# PCB_eLock_G592_J1_only_actuators.net
KiCad netlist of a schematic drawn in EAGLE
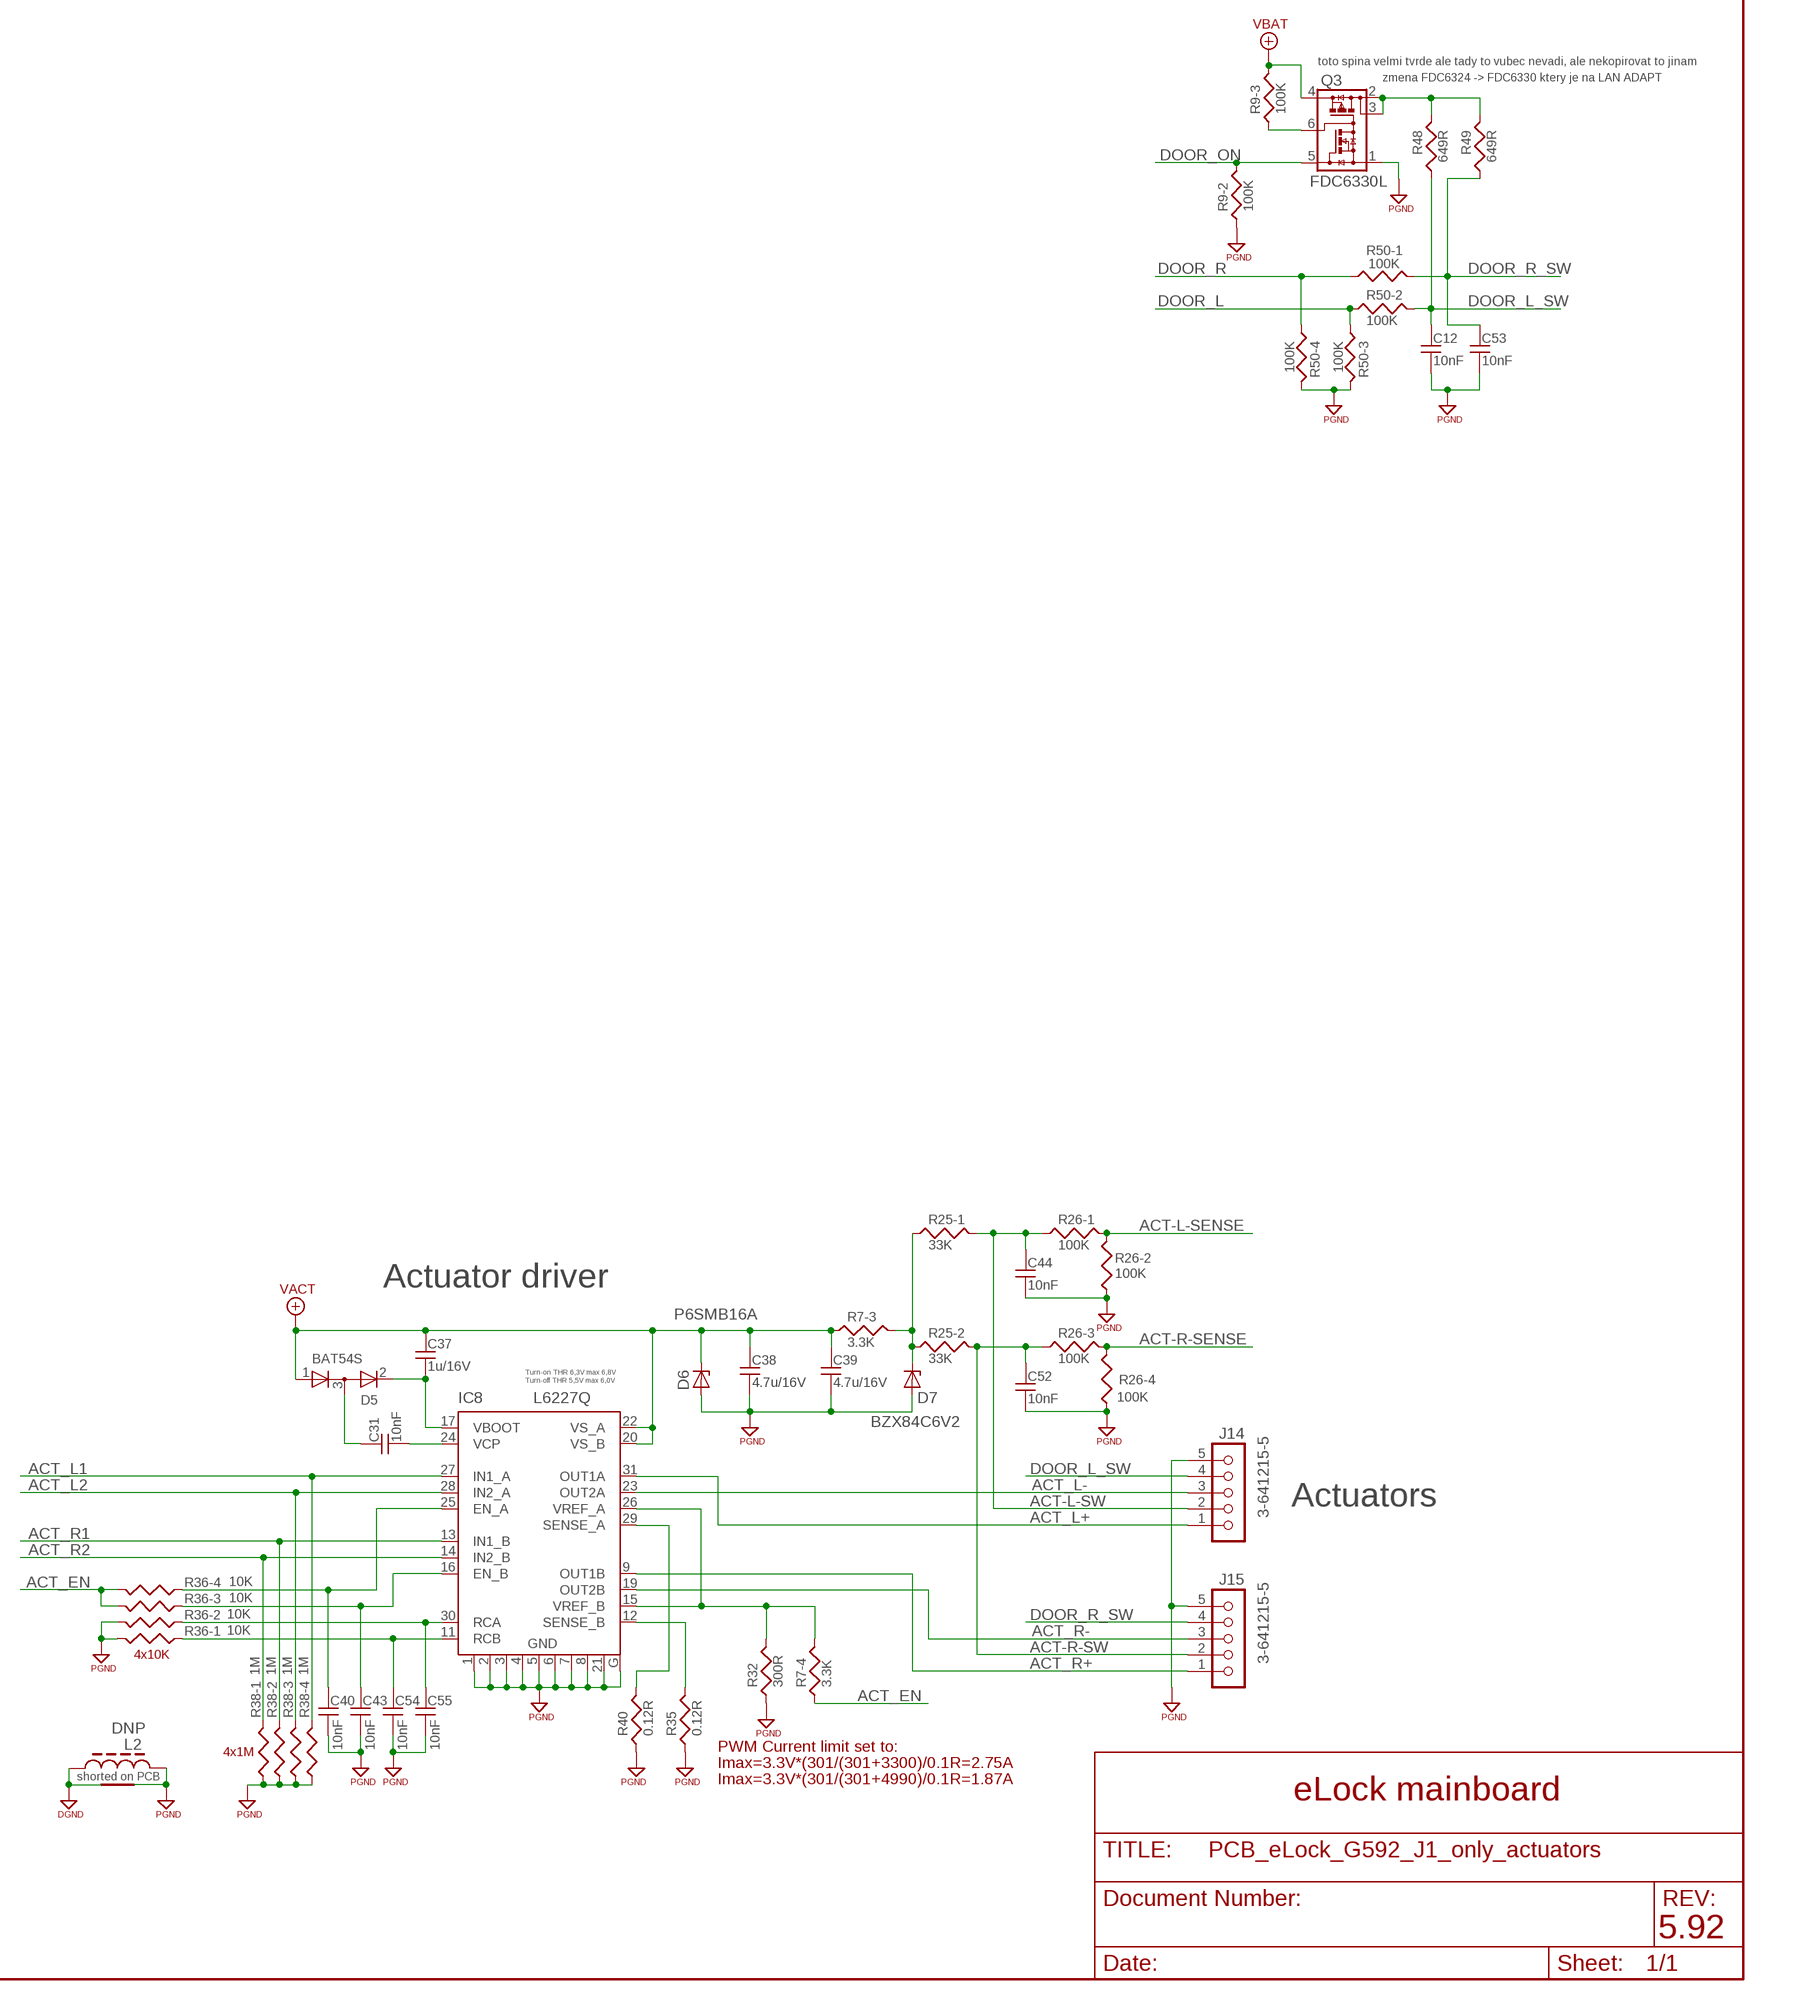
[diagram p0: schematic, sheet 1]

(export (version "E")
  (design (tool "Eeschema 10.0.6"))
  (components
    (comp (ref "C12")
      (value "10nF")
      (footprint "eagle-import:0603")
      (libsource (lib "eagle-import") (part "C-0603"))
    )
    (comp (ref "C31")
      (value "10nF")
      (footprint "eagle-import:0603")
      (libsource (lib "eagle-import") (part "C-0603"))
    )
    (comp (ref "C37")
      (value "1u/16V")
      (footprint "eagle-import:0603")
      (libsource (lib "eagle-import") (part "C-0603"))
    )
    (comp (ref "C38")
      (value "4.7u/16V")
      (footprint "eagle-import:0805")
      (libsource (lib "eagle-import") (part "C-0805"))
    )
    (comp (ref "C39")
      (value "4.7u/16V")
      (footprint "eagle-import:0805")
      (libsource (lib "eagle-import") (part "C-0805"))
    )
    (comp (ref "C40")
      (value "10nF")
      (footprint "eagle-import:0603")
      (libsource (lib "eagle-import") (part "C-0603"))
    )
    (comp (ref "C43")
      (value "10nF")
      (footprint "eagle-import:0603")
      (libsource (lib "eagle-import") (part "C-0603"))
    )
    (comp (ref "C44")
      (value "10nF")
      (footprint "eagle-import:0603")
      (libsource (lib "eagle-import") (part "C-0603"))
    )
    (comp (ref "C52")
      (value "10nF")
      (footprint "eagle-import:0603")
      (libsource (lib "eagle-import") (part "C-0603"))
    )
    (comp (ref "C53")
      (value "10nF")
      (footprint "eagle-import:0603")
      (libsource (lib "eagle-import") (part "C-0603"))
    )
    (comp (ref "C54")
      (value "10nF")
      (footprint "eagle-import:0603")
      (libsource (lib "eagle-import") (part "C-0603"))
    )
    (comp (ref "C55")
      (value "10nF")
      (footprint "eagle-import:0603")
      (libsource (lib "eagle-import") (part "C-0603"))
    )
    (comp (ref "D5")
      (value "BAT54S")
      (footprint "eagle-import:SOT-23")
      (libsource (lib "eagle-import") (part "BAT54S"))
    )
    (comp (ref "D6")
      (value "P6SMB16A")
      (footprint "eagle-import:SMB")
      (libsource (lib "eagle-import") (part "P6SMB16A"))
    )
    (comp (ref "D7")
      (value "BZX84C6V2")
      (footprint "eagle-import:SOT-23")
      (libsource (lib "eagle-import") (part "BZX84C6V2"))
    )
    (comp (ref "IC8")
      (value "L6227Q")
      (footprint "eagle-import:SQFP-S-5X5-32")
      (libsource (lib "eagle-import") (part "L6227Q"))
    )
    (comp (ref "J14")
      (value "3-641215-5")
      (footprint "eagle-import:3-641215-5")
      (libsource (lib "eagle-import") (part "3-641215-5"))
    )
    (comp (ref "J15")
      (value "3-641215-5")
      (footprint "eagle-import:3-641215-5")
      (libsource (lib "eagle-import") (part "3-641215-5"))
    )
    (comp (ref "L2")
      (value "DNP")
      (footprint "eagle-import:0805-0RTOP")
      (libsource (lib "eagle-import") (part "L-0805-0R"))
    )
    (comp (ref "Q3")
      (value "FDC6330L")
      (footprint "eagle-import:SSOT-6")
      (libsource (lib "eagle-import") (part "FDC6324L"))
    )
    (comp (ref "R7")
      (value "3.3K")
      (footprint "eagle-import:0603-ARRAY")
      (libsource (lib "eagle-import") (part "EXB-38"))
    )
    (comp (ref "R9")
      (value "100K")
      (footprint "eagle-import:0603-ARRAY")
      (libsource (lib "eagle-import") (part "EXB-38"))
    )
    (comp (ref "R25")
      (value "33K")
      (footprint "eagle-import:0603-ARRAY")
      (libsource (lib "eagle-import") (part "EXB-38"))
    )
    (comp (ref "R26")
      (value "100K")
      (footprint "eagle-import:0603-ARRAY")
      (libsource (lib "eagle-import") (part "EXB-38"))
    )
    (comp (ref "R32")
      (value "300R")
      (footprint "eagle-import:0603")
      (libsource (lib "eagle-import") (part "R-0603"))
    )
    (comp (ref "R35")
      (value "0.12R")
      (footprint "eagle-import:0805")
      (libsource (lib "eagle-import") (part "R-0805"))
    )
    (comp (ref "R36")
      (value "10K")
      (footprint "eagle-import:0603-ARRAY")
      (libsource (lib "eagle-import") (part "EXB-38"))
    )
    (comp (ref "R38")
      (value "1M")
      (footprint "eagle-import:0603-ARRAY")
      (libsource (lib "eagle-import") (part "EXB-38"))
    )
    (comp (ref "R40")
      (value "0.12R")
      (footprint "eagle-import:0805")
      (libsource (lib "eagle-import") (part "R-0805"))
    )
    (comp (ref "R48")
      (value "649R")
      (footprint "eagle-import:0603")
      (libsource (lib "eagle-import") (part "R-0603"))
    )
    (comp (ref "R49")
      (value "649R")
      (footprint "eagle-import:0603")
      (libsource (lib "eagle-import") (part "R-0603"))
    )
    (comp (ref "R50")
      (value "100K")
      (footprint "eagle-import:0603-ARRAY")
      (libsource (lib "eagle-import") (part "EXB-38"))
    )
  )
  (nets
    (net (code "1") (name "/ACT-L-SENSE") (class "Default")
      (node (ref "R26") (pin "7") (pinfunction "2_7") (pintype "passive"))
      (node (ref "R26") (pin "8") (pinfunction "2_8") (pintype "passive"))
    )
    (net (code "2") (name "/ACT-L-SW") (class "Default")
      (node (ref "C44") (pin "1") (pinfunction "1_1") (pintype "passive"))
      (node (ref "J14") (pin "2") (pinfunction "2_2") (pintype "passive"))
      (node (ref "R25") (pin "8") (pinfunction "2_8") (pintype "passive"))
      (node (ref "R26") (pin "1") (pinfunction "1_1") (pintype "passive"))
    )
    (net (code "3") (name "/ACT-R-SENSE") (class "Default")
      (node (ref "R26") (pin "5") (pinfunction "2_5") (pintype "passive"))
      (node (ref "R26") (pin "6") (pinfunction "2_6") (pintype "passive"))
    )
    (net (code "4") (name "/ACT-R-SW") (class "Default")
      (node (ref "C52") (pin "1") (pinfunction "1_1") (pintype "passive"))
      (node (ref "J15") (pin "2") (pinfunction "2_2") (pintype "passive"))
      (node (ref "R25") (pin "7") (pinfunction "2_7") (pintype "passive"))
      (node (ref "R26") (pin "3") (pinfunction "1_3") (pintype "passive"))
    )
    (net (code "5") (name "/ACT_EN") (class "Default")
      (node (ref "R36") (pin "5") (pinfunction "2_5") (pintype "passive"))
      (node (ref "R36") (pin "6") (pinfunction "2_6") (pintype "passive"))
      (node (ref "R7") (pin "4") (pinfunction "1_4") (pintype "passive"))
    )
    (net (code "6") (name "/ACT_L+") (class "Default")
      (node (ref "IC8") (pin "31") (pinfunction "OUT1A_31") (pintype "output"))
      (node (ref "J14") (pin "1") (pinfunction "1_1") (pintype "passive"))
    )
    (net (code "7") (name "/ACT_L-") (class "Default")
      (node (ref "IC8") (pin "23") (pinfunction "OUT2A_23") (pintype "output"))
      (node (ref "J14") (pin "3") (pinfunction "3_3") (pintype "passive"))
    )
    (net (code "8") (name "/ACT_L1") (class "Default")
      (node (ref "IC8") (pin "27") (pinfunction "IN1_A_27") (pintype "input"))
      (node (ref "R38") (pin "5") (pinfunction "2_5") (pintype "passive"))
    )
    (net (code "9") (name "/ACT_L2") (class "Default")
      (node (ref "IC8") (pin "28") (pinfunction "IN2_A_28") (pintype "input"))
      (node (ref "R38") (pin "6") (pinfunction "2_6") (pintype "passive"))
    )
    (net (code "10") (name "/ACT_R+") (class "Default")
      (node (ref "IC8") (pin "9") (pinfunction "OUT1B_9") (pintype "output"))
      (node (ref "J15") (pin "1") (pinfunction "1_1") (pintype "passive"))
    )
    (net (code "11") (name "/ACT_R-") (class "Default")
      (node (ref "IC8") (pin "19") (pinfunction "OUT2B_19") (pintype "output"))
      (node (ref "J15") (pin "3") (pinfunction "3_3") (pintype "passive"))
    )
    (net (code "12") (name "/ACT_R1") (class "Default")
      (node (ref "IC8") (pin "13") (pinfunction "IN1_B_13") (pintype "input"))
      (node (ref "R38") (pin "7") (pinfunction "2_7") (pintype "passive"))
    )
    (net (code "13") (name "/ACT_R2") (class "Default")
      (node (ref "IC8") (pin "14") (pinfunction "IN2_B_14") (pintype "input"))
      (node (ref "R38") (pin "8") (pinfunction "2_8") (pintype "passive"))
    )
    (net (code "14") (name "/DOOR_L") (class "Default")
      (node (ref "R50") (pin "2") (pinfunction "1_2") (pintype "passive"))
      (node (ref "R50") (pin "3") (pinfunction "1_3") (pintype "passive"))
    )
    (net (code "15") (name "/DOOR_L_SW") (class "Default")
      (node (ref "C12") (pin "1") (pinfunction "1_1") (pintype "passive"))
      (node (ref "J14") (pin "4") (pinfunction "4_4") (pintype "passive"))
      (node (ref "R48") (pin "2") (pinfunction "2_2") (pintype "passive"))
      (node (ref "R50") (pin "7") (pinfunction "2_7") (pintype "passive"))
    )
    (net (code "16") (name "/DOOR_ON") (class "Default")
      (node (ref "Q3") (pin "5") (pinfunction "Q1G_5") (pintype "input"))
      (node (ref "R9") (pin "7") (pinfunction "2_7") (pintype "passive"))
    )
    (net (code "17") (name "/DOOR_R") (class "Default")
      (node (ref "R50") (pin "1") (pinfunction "1_1") (pintype "passive"))
      (node (ref "R50") (pin "4") (pinfunction "1_4") (pintype "passive"))
    )
    (net (code "18") (name "/DOOR_R_SW") (class "Default")
      (node (ref "C53") (pin "1") (pinfunction "1_1") (pintype "passive"))
      (node (ref "J15") (pin "4") (pinfunction "4_4") (pintype "passive"))
      (node (ref "R49") (pin "2") (pinfunction "2_2") (pintype "passive"))
      (node (ref "R50") (pin "8") (pinfunction "2_8") (pintype "passive"))
    )
    (net (code "19") (name "DGND") (class "Default")
      (node (ref "L2") (pin "2") (pinfunction "2_2") (pintype "passive"))
    )
    (net (code "20") (name "Net-(D5-K)") (class "Default")
      (node (ref "C37") (pin "2") (pinfunction "2_2") (pintype "passive"))
      (node (ref "D5") (pin "2") (pinfunction "K_2") (pintype "passive"))
      (node (ref "IC8") (pin "17") (pinfunction "VBOOT_17") (pintype "input"))
    )
    (net (code "21") (name "Net-(D5-KA)") (class "Default")
      (node (ref "C31") (pin "1") (pinfunction "1_1") (pintype "passive"))
      (node (ref "D5") (pin "3") (pinfunction "KA_3") (pintype "passive"))
    )
    (net (code "22") (name "Net-(D7-C)") (class "Default")
      (node (ref "D7") (pin "3") (pinfunction "C_3") (pintype "passive"))
      (node (ref "R25") (pin "1") (pinfunction "1_1") (pintype "passive"))
      (node (ref "R25") (pin "2") (pinfunction "1_2") (pintype "passive"))
      (node (ref "R7") (pin "6") (pinfunction "2_6") (pintype "passive"))
    )
    (net (code "23") (name "Net-(IC8-EN_A)") (class "Default")
      (node (ref "C40") (pin "1") (pinfunction "1_1") (pintype "passive"))
      (node (ref "IC8") (pin "25") (pinfunction "EN_A_25") (pintype "input"))
      (node (ref "R36") (pin "4") (pinfunction "1_4") (pintype "passive"))
    )
    (net (code "24") (name "Net-(IC8-EN_B)") (class "Default")
      (node (ref "C43") (pin "1") (pinfunction "1_1") (pintype "passive"))
      (node (ref "IC8") (pin "16") (pinfunction "EN_B_16") (pintype "input"))
      (node (ref "R36") (pin "3") (pinfunction "1_3") (pintype "passive"))
    )
    (net (code "25") (name "Net-(IC8-RCA)") (class "Default")
      (node (ref "C55") (pin "1") (pinfunction "1_1") (pintype "passive"))
      (node (ref "IC8") (pin "30") (pinfunction "RCA_30") (pintype "input"))
      (node (ref "R36") (pin "2") (pinfunction "1_2") (pintype "passive"))
    )
    (net (code "26") (name "Net-(IC8-RCB)") (class "Default")
      (node (ref "C54") (pin "1") (pinfunction "1_1") (pintype "passive"))
      (node (ref "IC8") (pin "11") (pinfunction "RCB_11") (pintype "input"))
      (node (ref "R36") (pin "1") (pinfunction "1_1") (pintype "passive"))
    )
    (net (code "27") (name "Net-(IC8-SENSE_A)") (class "Default")
      (node (ref "IC8") (pin "29") (pinfunction "SENSE_A_29") (pintype "input"))
      (node (ref "R40") (pin "2") (pinfunction "2_2") (pintype "passive"))
    )
    (net (code "28") (name "Net-(IC8-SENSE_B)") (class "Default")
      (node (ref "IC8") (pin "12") (pinfunction "SENSE_B_12") (pintype "input"))
      (node (ref "R35") (pin "2") (pinfunction "2_2") (pintype "passive"))
    )
    (net (code "29") (name "Net-(IC8-VCP)") (class "Default")
      (node (ref "C31") (pin "2") (pinfunction "2_2") (pintype "passive"))
      (node (ref "IC8") (pin "24") (pinfunction "VCP_24") (pintype "input"))
    )
    (net (code "30") (name "Net-(IC8-VREF_A)") (class "Default")
      (node (ref "IC8") (pin "15") (pinfunction "VREF_B_15") (pintype "input"))
      (node (ref "IC8") (pin "26") (pinfunction "VREF_A_26") (pintype "input"))
      (node (ref "R32") (pin "2") (pinfunction "2_2") (pintype "passive"))
      (node (ref "R7") (pin "5") (pinfunction "2_5") (pintype "passive"))
    )
    (net (code "31") (name "Net-(Q3-Q2D1)") (class "Default")
      (node (ref "Q3") (pin "2") (pinfunction "Q2D1_2") (pintype "bidirectional"))
      (node (ref "Q3") (pin "3") (pinfunction "Q2D2_3") (pintype "bidirectional"))
      (node (ref "R48") (pin "1") (pinfunction "1_1") (pintype "passive"))
      (node (ref "R49") (pin "1") (pinfunction "1_1") (pintype "passive"))
    )
    (net (code "32") (name "Net-(Q3-Q2G)") (class "Default")
      (node (ref "Q3") (pin "6") (pinfunction "Q2G_6") (pintype "input"))
      (node (ref "R9") (pin "3") (pinfunction "1_3") (pintype "passive"))
    )
    (net (code "33") (name "PGND") (class "Default")
      (node (ref "C12") (pin "2") (pinfunction "2_2") (pintype "passive"))
      (node (ref "C38") (pin "2") (pinfunction "2_2") (pintype "passive"))
      (node (ref "C39") (pin "2") (pinfunction "2_2") (pintype "passive"))
      (node (ref "C40") (pin "2") (pinfunction "2_2") (pintype "passive"))
      (node (ref "C43") (pin "2") (pinfunction "2_2") (pintype "passive"))
      (node (ref "C44") (pin "2") (pinfunction "2_2") (pintype "passive"))
      (node (ref "C52") (pin "2") (pinfunction "2_2") (pintype "passive"))
      (node (ref "C53") (pin "2") (pinfunction "2_2") (pintype "passive"))
      (node (ref "C54") (pin "2") (pinfunction "2_2") (pintype "passive"))
      (node (ref "C55") (pin "2") (pinfunction "2_2") (pintype "passive"))
      (node (ref "D6") (pin "A") (pinfunction "A_A") (pintype "passive"))
      (node (ref "D7") (pin "1") (pinfunction "A_1") (pintype "passive"))
      (node (ref "IC8") (pin "1") (pinfunction "GND1_1") (pintype "input"))
      (node (ref "IC8") (pin "2") (pinfunction "GND2_2") (pintype "input"))
      (node (ref "IC8") (pin "21") (pinfunction "GND21_21") (pintype "input"))
      (node (ref "IC8") (pin "3") (pinfunction "GND3_3") (pintype "input"))
      (node (ref "IC8") (pin "4") (pinfunction "GND4_4") (pintype "input"))
      (node (ref "IC8") (pin "5") (pinfunction "GND5_5") (pintype "input"))
      (node (ref "IC8") (pin "6") (pinfunction "GND6_6") (pintype "input"))
      (node (ref "IC8") (pin "7") (pinfunction "GND7_7") (pintype "input"))
      (node (ref "IC8") (pin "8") (pinfunction "GND8_8") (pintype "input"))
      (node (ref "IC8") (pin "G") (pinfunction "GNEXP_G") (pintype "input"))
      (node (ref "J14") (pin "5") (pinfunction "5_5") (pintype "passive"))
      (node (ref "J15") (pin "5") (pinfunction "5_5") (pintype "passive"))
      (node (ref "L2") (pin "1") (pinfunction "1_1") (pintype "passive"))
      (node (ref "Q3") (pin "1") (pinfunction "Q1S_1") (pintype "bidirectional"))
      (node (ref "R26") (pin "2") (pinfunction "1_2") (pintype "passive"))
      (node (ref "R26") (pin "4") (pinfunction "1_4") (pintype "passive"))
      (node (ref "R32") (pin "1") (pinfunction "1_1") (pintype "passive"))
      (node (ref "R35") (pin "1") (pinfunction "1_1") (pintype "passive"))
      (node (ref "R36") (pin "7") (pinfunction "2_7") (pintype "passive"))
      (node (ref "R36") (pin "8") (pinfunction "2_8") (pintype "passive"))
      (node (ref "R38") (pin "1") (pinfunction "1_1") (pintype "passive"))
      (node (ref "R38") (pin "2") (pinfunction "1_2") (pintype "passive"))
      (node (ref "R38") (pin "3") (pinfunction "1_3") (pintype "passive"))
      (node (ref "R38") (pin "4") (pinfunction "1_4") (pintype "passive"))
      (node (ref "R40") (pin "1") (pinfunction "1_1") (pintype "passive"))
      (node (ref "R50") (pin "5") (pinfunction "2_5") (pintype "passive"))
      (node (ref "R50") (pin "6") (pinfunction "2_6") (pintype "passive"))
      (node (ref "R9") (pin "2") (pinfunction "1_2") (pintype "passive"))
    )
    (net (code "34") (name "VACT") (class "Default")
      (node (ref "C37") (pin "1") (pinfunction "1_1") (pintype "passive"))
      (node (ref "C38") (pin "1") (pinfunction "1_1") (pintype "passive"))
      (node (ref "C39") (pin "1") (pinfunction "1_1") (pintype "passive"))
      (node (ref "D5") (pin "1") (pinfunction "A_1") (pintype "passive"))
      (node (ref "D6") (pin "C") (pinfunction "C_C") (pintype "passive"))
      (node (ref "IC8") (pin "20") (pinfunction "VS_B_20") (pintype "input"))
      (node (ref "IC8") (pin "22") (pinfunction "VS_A_22") (pintype "input"))
      (node (ref "R7") (pin "3") (pinfunction "1_3") (pintype "passive"))
    )
    (net (code "35") (name "VBAT") (class "Default")
      (node (ref "Q3") (pin "4") (pinfunction "Q2S_4") (pintype "bidirectional"))
      (node (ref "R9") (pin "6") (pinfunction "2_6") (pintype "passive"))
    )
  )
)
